# CON_LCD_INDM.net
KiCad netlist of a schematic drawn in Altium Designer
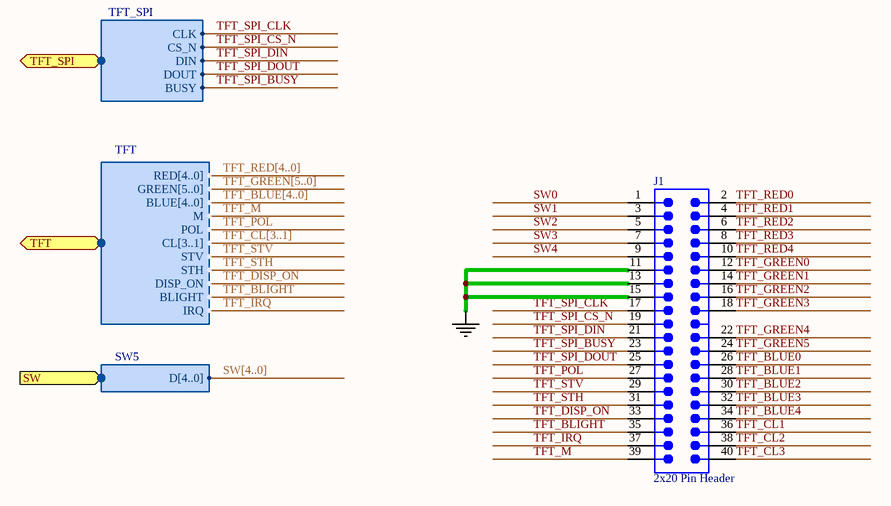
[diagram p0: CON_LCD_INDM.SchDoc]

(export (version "E")
  (design (tool "Eeschema 10.0.6"))
  (components
    (comp (ref "J1")
      (value "2x20 Pin Header")
      (footprint "HDR2X20")
      (description "Header, IDC, 2x20 pin Vertical")
      (libsource (lib "AltiumDesignLibrary") (part "CON-IDC-2x20-M-STR"))
    )
  )
  (nets
    (net (code "4") (name "/SW0") (class "Default")
      (node (ref "J1") (pin "1") (pinfunction "1_1") (pintype "passive"))
    )
    (net (code "5") (name "/SW1") (class "Default")
      (node (ref "J1") (pin "3") (pinfunction "3_3") (pintype "passive"))
    )
    (net (code "6") (name "/SW2") (class "Default")
      (node (ref "J1") (pin "5") (pinfunction "5_5") (pintype "passive"))
    )
    (net (code "7") (name "/SW3") (class "Default")
      (node (ref "J1") (pin "7") (pinfunction "7_7") (pintype "passive"))
    )
    (net (code "8") (name "/SW4") (class "Default")
      (node (ref "J1") (pin "9") (pinfunction "9_9") (pintype "passive"))
    )
    (net (code "10") (name "/TFT_BLIGHT") (class "Default")
      (node (ref "J1") (pin "35") (pinfunction "35_35") (pintype "passive"))
    )
    (net (code "11") (name "/TFT_BLUE0") (class "Default")
      (node (ref "J1") (pin "26") (pinfunction "26_26") (pintype "passive"))
    )
    (net (code "12") (name "/TFT_BLUE1") (class "Default")
      (node (ref "J1") (pin "28") (pinfunction "28_28") (pintype "passive"))
    )
    (net (code "13") (name "/TFT_BLUE2") (class "Default")
      (node (ref "J1") (pin "30") (pinfunction "30_30") (pintype "passive"))
    )
    (net (code "14") (name "/TFT_BLUE3") (class "Default")
      (node (ref "J1") (pin "32") (pinfunction "32_32") (pintype "passive"))
    )
    (net (code "15") (name "/TFT_BLUE4") (class "Default")
      (node (ref "J1") (pin "34") (pinfunction "34_34") (pintype "passive"))
    )
    (net (code "17") (name "/TFT_CL1") (class "Default")
      (node (ref "J1") (pin "36") (pinfunction "36_36") (pintype "passive"))
    )
    (net (code "18") (name "/TFT_CL2") (class "Default")
      (node (ref "J1") (pin "38") (pinfunction "38_38") (pintype "passive"))
    )
    (net (code "19") (name "/TFT_CL3") (class "Default")
      (node (ref "J1") (pin "40") (pinfunction "40_40") (pintype "passive"))
    )
    (net (code "20") (name "/TFT_DISP_ON") (class "Default")
      (node (ref "J1") (pin "33") (pinfunction "33_33") (pintype "passive"))
    )
    (net (code "21") (name "/TFT_GREEN0") (class "Default")
      (node (ref "J1") (pin "12") (pinfunction "12_12") (pintype "passive"))
    )
    (net (code "22") (name "/TFT_GREEN1") (class "Default")
      (node (ref "J1") (pin "14") (pinfunction "14_14") (pintype "passive"))
    )
    (net (code "23") (name "/TFT_GREEN2") (class "Default")
      (node (ref "J1") (pin "16") (pinfunction "16_16") (pintype "passive"))
    )
    (net (code "24") (name "/TFT_GREEN3") (class "Default")
      (node (ref "J1") (pin "18") (pinfunction "18_18") (pintype "passive"))
    )
    (net (code "25") (name "/TFT_GREEN4") (class "Default")
      (node (ref "J1") (pin "22") (pinfunction "22_22") (pintype "passive"))
    )
    (net (code "26") (name "/TFT_GREEN5") (class "Default")
      (node (ref "J1") (pin "24") (pinfunction "24_24") (pintype "passive"))
    )
    (net (code "28") (name "/TFT_IRQ") (class "Default")
      (node (ref "J1") (pin "37") (pinfunction "37_37") (pintype "passive"))
    )
    (net (code "29") (name "/TFT_M") (class "Default")
      (node (ref "J1") (pin "39") (pinfunction "39_39") (pintype "passive"))
    )
    (net (code "30") (name "/TFT_POL") (class "Default")
      (node (ref "J1") (pin "27") (pinfunction "27_27") (pintype "passive"))
    )
    (net (code "31") (name "/TFT_RED0") (class "Default")
      (node (ref "J1") (pin "2") (pinfunction "2_2") (pintype "passive"))
    )
    (net (code "32") (name "/TFT_RED1") (class "Default")
      (node (ref "J1") (pin "4") (pinfunction "4_4") (pintype "passive"))
    )
    (net (code "33") (name "/TFT_RED2") (class "Default")
      (node (ref "J1") (pin "6") (pinfunction "6_6") (pintype "passive"))
    )
    (net (code "34") (name "/TFT_RED3") (class "Default")
      (node (ref "J1") (pin "8") (pinfunction "8_8") (pintype "passive"))
    )
    (net (code "35") (name "/TFT_RED4") (class "Default")
      (node (ref "J1") (pin "10") (pinfunction "10_10") (pintype "passive"))
    )
    (net (code "37") (name "/TFT_SPI_BUSY") (class "Default")
      (node (ref "J1") (pin "23") (pinfunction "23_23") (pintype "passive"))
    )
    (net (code "38") (name "/TFT_SPI_CLK") (class "Default")
      (node (ref "J1") (pin "17") (pinfunction "17_17") (pintype "passive"))
    )
    (net (code "39") (name "/TFT_SPI_CS_N") (class "Default")
      (node (ref "J1") (pin "19") (pinfunction "19_19") (pintype "passive"))
    )
    (net (code "40") (name "/TFT_SPI_DIN") (class "Default")
      (node (ref "J1") (pin "21") (pinfunction "21_21") (pintype "passive"))
    )
    (net (code "41") (name "/TFT_SPI_DOUT") (class "Default")
      (node (ref "J1") (pin "25") (pinfunction "25_25") (pintype "passive"))
    )
    (net (code "42") (name "/TFT_STH") (class "Default")
      (node (ref "J1") (pin "31") (pinfunction "31_31") (pintype "passive"))
    )
    (net (code "43") (name "/TFT_STV") (class "Default")
      (node (ref "J1") (pin "29") (pinfunction "29_29") (pintype "passive"))
    )
    (net (code "48") (name "GND") (class "Default")
      (node (ref "J1") (pin "11") (pinfunction "11_11") (pintype "passive"))
      (node (ref "J1") (pin "13") (pinfunction "13_13") (pintype "passive"))
      (node (ref "J1") (pin "15") (pinfunction "15_15") (pintype "passive"))
    )
  )
)
